# openLRS-APM.net
KiCad netlist of a schematic drawn in EAGLE
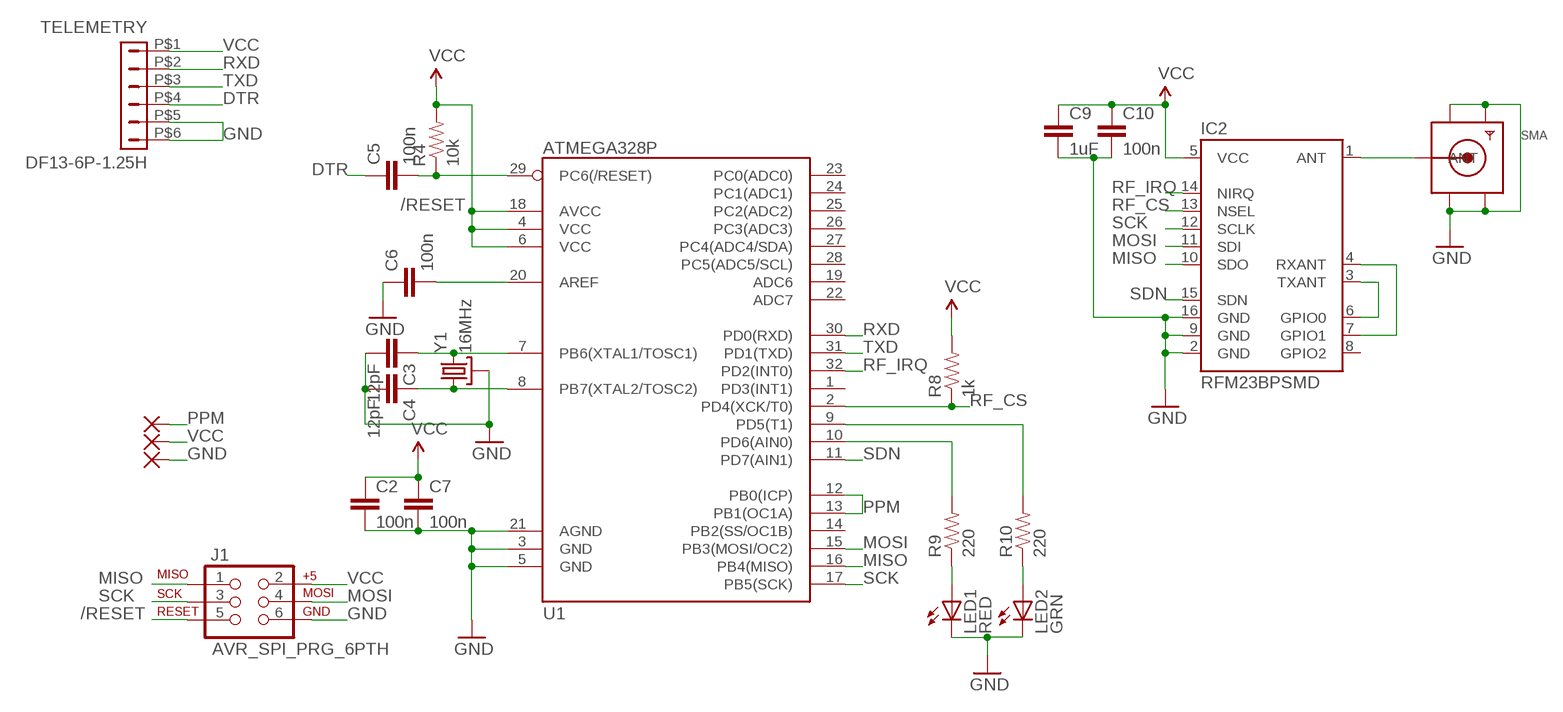
[diagram p0: schematic, sheet 1]

(export (version "E")
  (design (tool "Eeschema 10.0.6"))
  (components
    (comp (ref "C2")
      (value "100n")
      (footprint "eagle-import:0805")
      (libsource (lib "eagle-import") (part "CAP0805"))
    )
    (comp (ref "C3")
      (value "12pF")
      (footprint "eagle-import:0805")
      (libsource (lib "eagle-import") (part "CAP0805"))
    )
    (comp (ref "C4")
      (value "12pF")
      (footprint "eagle-import:0805")
      (libsource (lib "eagle-import") (part "CAP0805"))
    )
    (comp (ref "C5")
      (value "100n")
      (footprint "eagle-import:0805")
      (libsource (lib "eagle-import") (part "CAP0805"))
    )
    (comp (ref "C6")
      (value "100n")
      (footprint "eagle-import:0805")
      (libsource (lib "eagle-import") (part "CAP0805"))
    )
    (comp (ref "C7")
      (value "100n")
      (footprint "eagle-import:0805")
      (libsource (lib "eagle-import") (part "CAP0805"))
    )
    (comp (ref "C9")
      (value "1uF")
      (footprint "eagle-import:0805")
      (libsource (lib "eagle-import") (part "CAP0805"))
    )
    (comp (ref "C10")
      (value "100n")
      (footprint "eagle-import:0805")
      (libsource (lib "eagle-import") (part "CAP0805"))
    )
    (comp (ref "GND")
      (value "WIREPADSMD1,27-254")
      (footprint "eagle-import:SMD1,27-2,54")
      (libsource (lib "eagle-import") (part "WIREPADSMD1,27-254"))
    )
    (comp (ref "IC2")
      (value "RFM23BPSMD")
      (footprint "eagle-import:RFM23BP-S2")
      (libsource (lib "eagle-import") (part "RFM23BPSMD"))
    )
    (comp (ref "J1")
      (value "AVR_SPI_PRG_6PTH")
      (footprint "eagle-import:2X3")
      (libsource (lib "eagle-import") (part "AVR_SPI_PRG_6PTH"))
    )
    (comp (ref "LED1")
      (value "RED")
      (footprint "eagle-import:SML0805")
      (libsource (lib "eagle-import") (part "LEDSML0805"))
    )
    (comp (ref "LED2")
      (value "GRN")
      (footprint "eagle-import:SML0805")
      (libsource (lib "eagle-import") (part "LEDSML0805"))
    )
    (comp (ref "PPM")
      (value "WIREPADSMD1,27-254")
      (footprint "eagle-import:SMD1,27-2,54")
      (libsource (lib "eagle-import") (part "WIREPADSMD1,27-254"))
    )
    (comp (ref "R4")
      (value "10k")
      (footprint "eagle-import:0805")
      (libsource (lib "eagle-import") (part "RESISTOR0805-RES"))
    )
    (comp (ref "R8")
      (value "1k")
      (footprint "eagle-import:0805")
      (libsource (lib "eagle-import") (part "RESISTOR0805-RES"))
    )
    (comp (ref "R9")
      (value "220")
      (footprint "eagle-import:0805")
      (libsource (lib "eagle-import") (part "RESISTOR0805-RES"))
    )
    (comp (ref "R10")
      (value "220")
      (footprint "eagle-import:0805")
      (libsource (lib "eagle-import") (part "RESISTOR0805-RES"))
    )
    (comp (ref "SMA")
      (value "SMACONNECTOR_EDGE")
      (footprint "eagle-import:SMA_EDGELAUNCH")
      (libsource (lib "eagle-import") (part "SMACONNECTOR_EDGE"))
    )
    (comp (ref "TELEMETRY")
      (value "DF13-6P-1.25H")
      (footprint "eagle-import:DF13A-6P-1.25H")
      (libsource (lib "eagle-import") (part "DF13-6P-1.25H"))
    )
    (comp (ref "U1")
      (value "ATMEGA328P")
      (footprint "eagle-import:TQFP32-08")
      (libsource (lib "eagle-import") (part "ATMEGA328_SMT"))
    )
    (comp (ref "VCC")
      (value "WIREPADSMD1,27-254")
      (footprint "eagle-import:SMD1,27-2,54")
      (libsource (lib "eagle-import") (part "WIREPADSMD1,27-254"))
    )
    (comp (ref "Y1")
      (value "16MHz")
      (footprint "eagle-import:CRYSTAL-SMD-5X3")
      (libsource (lib "eagle-import") (part "CRYSTAL3.2X2.5"))
    )
  )
  (nets
    (net (code "1") (name "/DTR") (class "Default")
      (node (ref "C5") (pin "1") (pinfunction "1_1") (pintype "passive"))
      (node (ref "TELEMETRY") (pin "P$4") (pinfunction "4_P$4") (pintype "passive"))
    )
    (net (code "2") (name "/MISO") (class "Default")
      (node (ref "IC2") (pin "10") (pinfunction "SDO_10") (pintype "output"))
      (node (ref "J1") (pin "1") (pinfunction "1_1") (pintype "passive"))
      (node (ref "U1") (pin "16") (pinfunction "PB4(MISO)_16") (pintype "bidirectional"))
    )
    (net (code "3") (name "/MOSI") (class "Default")
      (node (ref "IC2") (pin "11") (pinfunction "SDI_11") (pintype "input"))
      (node (ref "J1") (pin "4") (pinfunction "4_4") (pintype "passive"))
      (node (ref "U1") (pin "15") (pinfunction "PB3(MOSI/OC2)_15") (pintype "bidirectional"))
    )
    (net (code "4") (name "/PPM") (class "Default")
      (node (ref "PPM") (pin "1") (pinfunction "P_1") (pintype "passive"))
      (node (ref "U1") (pin "12") (pinfunction "PB0(ICP)_12") (pintype "bidirectional"))
      (node (ref "U1") (pin "13") (pinfunction "PB1(OC1A)_13") (pintype "bidirectional"))
    )
    (net (code "5") (name "/RF_CS") (class "Default")
      (node (ref "IC2") (pin "13") (pinfunction "NSEL_13") (pintype "input"))
      (node (ref "R8") (pin "1") (pinfunction "1_1") (pintype "passive"))
      (node (ref "U1") (pin "2") (pinfunction "PD4(XCK/T0)_2") (pintype "bidirectional"))
    )
    (net (code "6") (name "/RF_IRQ") (class "Default")
      (node (ref "IC2") (pin "14") (pinfunction "NIRQ_14") (pintype "output"))
      (node (ref "U1") (pin "32") (pinfunction "PD2(INT0)_32") (pintype "bidirectional"))
    )
    (net (code "7") (name "/RXD") (class "Default")
      (node (ref "TELEMETRY") (pin "P$2") (pinfunction "2_P$2") (pintype "passive"))
      (node (ref "U1") (pin "30") (pinfunction "PD0(RXD)_30") (pintype "bidirectional"))
    )
    (net (code "8") (name "/SCK") (class "Default")
      (node (ref "IC2") (pin "12") (pinfunction "SCLK_12") (pintype "input"))
      (node (ref "J1") (pin "3") (pinfunction "3_3") (pintype "passive"))
      (node (ref "U1") (pin "17") (pinfunction "PB5(SCK)_17") (pintype "bidirectional"))
    )
    (net (code "9") (name "/SDN") (class "Default")
      (node (ref "IC2") (pin "15") (pinfunction "SDN_15") (pintype "input"))
      (node (ref "U1") (pin "11") (pinfunction "PD7(AIN1)_11") (pintype "bidirectional"))
    )
    (net (code "10") (name "/TXD") (class "Default")
      (node (ref "TELEMETRY") (pin "P$3") (pinfunction "3_P$3") (pintype "passive"))
      (node (ref "U1") (pin "31") (pinfunction "PD1(TXD)_31") (pintype "bidirectional"))
    )
    (net (code "11") (name "/{slash}RESET") (class "Default")
      (node (ref "C5") (pin "2") (pinfunction "2_2") (pintype "passive"))
      (node (ref "J1") (pin "5") (pinfunction "5_5") (pintype "passive"))
      (node (ref "R4") (pin "1") (pinfunction "1_1") (pintype "passive"))
      (node (ref "U1") (pin "29") (pinfunction "PC6(/RESET)_29") (pintype "bidirectional"))
    )
    (net (code "12") (name "GND") (class "Default")
      (node (ref "C10") (pin "2") (pinfunction "2_2") (pintype "passive"))
      (node (ref "C2") (pin "2") (pinfunction "2_2") (pintype "passive"))
      (node (ref "C3") (pin "2") (pinfunction "2_2") (pintype "passive"))
      (node (ref "C4") (pin "2") (pinfunction "2_2") (pintype "passive"))
      (node (ref "C6") (pin "1") (pinfunction "1_1") (pintype "passive"))
      (node (ref "C7") (pin "2") (pinfunction "2_2") (pintype "passive"))
      (node (ref "C9") (pin "2") (pinfunction "2_2") (pintype "passive"))
      (node (ref "GND") (pin "1") (pinfunction "P_1") (pintype "passive"))
      (node (ref "IC2") (pin "16") (pinfunction "GND_16") (pintype "power_in"))
      (node (ref "IC2") (pin "2") (pinfunction "GND_2") (pintype "power_in"))
      (node (ref "IC2") (pin "9") (pinfunction "GND_9") (pintype "power_in"))
      (node (ref "J1") (pin "6") (pinfunction "6_6") (pintype "passive"))
      (node (ref "LED1") (pin "C") (pinfunction "C_C") (pintype "passive"))
      (node (ref "LED2") (pin "C") (pinfunction "C_C") (pintype "passive"))
      (node (ref "SMA") (pin "GND@1") (pinfunction "GND4_GND@1") (pintype "power_in"))
      (node (ref "SMA") (pin "GND@2") (pinfunction "GND3_GND@2") (pintype "power_in"))
      (node (ref "SMA") (pin "GND@3") (pinfunction "GND2_GND@3") (pintype "power_in"))
      (node (ref "SMA") (pin "GND@4") (pinfunction "GND1_GND@4") (pintype "power_in"))
      (node (ref "TELEMETRY") (pin "P$5") (pinfunction "5_P$5") (pintype "passive"))
      (node (ref "TELEMETRY") (pin "P$6") (pinfunction "6_P$6") (pintype "passive"))
      (node (ref "U1") (pin "21") (pinfunction "AGND_21") (pintype "bidirectional"))
      (node (ref "U1") (pin "3") (pinfunction "GND_3") (pintype "bidirectional"))
      (node (ref "U1") (pin "5") (pinfunction "GND_5") (pintype "bidirectional"))
      (node (ref "Y1") (pin "2") (pinfunction "GND_2") (pintype "power_in"))
      (node (ref "Y1") (pin "4") (pinfunction "GND_4") (pintype "power_in"))
    )
    (net (code "13") (name "Net-(IC2-ANT)") (class "Default")
      (node (ref "IC2") (pin "1") (pinfunction "ANT_1") (pintype "bidirectional"))
      (node (ref "SMA") (pin "P") (pinfunction "ANT_P") (pintype "bidirectional"))
    )
    (net (code "14") (name "Net-(IC2-GPIO0)") (class "Default")
      (node (ref "IC2") (pin "3") (pinfunction "TXANT_3") (pintype "input"))
      (node (ref "IC2") (pin "6") (pinfunction "GPIO0_6") (pintype "bidirectional"))
    )
    (net (code "15") (name "Net-(IC2-GPIO1)") (class "Default")
      (node (ref "IC2") (pin "4") (pinfunction "RXANT_4") (pintype "input"))
      (node (ref "IC2") (pin "7") (pinfunction "GPIO1_7") (pintype "bidirectional"))
    )
    (net (code "16") (name "Net-(LED1-PadA)") (class "Default")
      (node (ref "LED1") (pin "A") (pinfunction "A_A") (pintype "passive"))
      (node (ref "R9") (pin "1") (pinfunction "1_1") (pintype "passive"))
    )
    (net (code "17") (name "Net-(LED2-PadA)") (class "Default")
      (node (ref "LED2") (pin "A") (pinfunction "A_A") (pintype "passive"))
      (node (ref "R10") (pin "1") (pinfunction "1_1") (pintype "passive"))
    )
    (net (code "18") (name "Net-(U1-AREF)") (class "Default")
      (node (ref "C6") (pin "2") (pinfunction "2_2") (pintype "passive"))
      (node (ref "U1") (pin "20") (pinfunction "AREF_20") (pintype "bidirectional"))
    )
    (net (code "19") (name "Net-(U1-PB6(XTAL1{slash}TOSC1))") (class "Default")
      (node (ref "C3") (pin "1") (pinfunction "1_1") (pintype "passive"))
      (node (ref "U1") (pin "7") (pinfunction "PB6(XTAL1/TOSC1)_7") (pintype "bidirectional"))
      (node (ref "Y1") (pin "3") (pinfunction "2_3") (pintype "passive"))
    )
    (net (code "20") (name "Net-(U1-PB7(XTAL2{slash}TOSC2))") (class "Default")
      (node (ref "C4") (pin "1") (pinfunction "1_1") (pintype "passive"))
      (node (ref "U1") (pin "8") (pinfunction "PB7(XTAL2/TOSC2)_8") (pintype "bidirectional"))
      (node (ref "Y1") (pin "1") (pinfunction "1_1") (pintype "passive"))
    )
    (net (code "21") (name "Net-(U1-PD5(T1))") (class "Default")
      (node (ref "R10") (pin "2") (pinfunction "2_2") (pintype "passive"))
      (node (ref "U1") (pin "9") (pinfunction "PD5(T1)_9") (pintype "bidirectional"))
    )
    (net (code "22") (name "Net-(U1-PD6(AIN0))") (class "Default")
      (node (ref "R9") (pin "2") (pinfunction "2_2") (pintype "passive"))
      (node (ref "U1") (pin "10") (pinfunction "PD6(AIN0)_10") (pintype "bidirectional"))
    )
    (net (code "23") (name "VCC") (class "Default")
      (node (ref "C10") (pin "1") (pinfunction "1_1") (pintype "passive"))
      (node (ref "C2") (pin "1") (pinfunction "1_1") (pintype "passive"))
      (node (ref "C7") (pin "1") (pinfunction "1_1") (pintype "passive"))
      (node (ref "C9") (pin "1") (pinfunction "1_1") (pintype "passive"))
      (node (ref "IC2") (pin "5") (pinfunction "VCC_5") (pintype "bidirectional"))
      (node (ref "J1") (pin "2") (pinfunction "2_2") (pintype "passive"))
      (node (ref "R4") (pin "2") (pinfunction "2_2") (pintype "passive"))
      (node (ref "R8") (pin "2") (pinfunction "2_2") (pintype "passive"))
      (node (ref "TELEMETRY") (pin "P$1") (pinfunction "1_P$1") (pintype "passive"))
      (node (ref "U1") (pin "18") (pinfunction "AVCC_18") (pintype "bidirectional"))
      (node (ref "U1") (pin "4") (pinfunction "VCC_4") (pintype "bidirectional"))
      (node (ref "U1") (pin "6") (pinfunction "VCC_6") (pintype "bidirectional"))
      (node (ref "VCC") (pin "1") (pinfunction "P_1") (pintype "passive"))
    )
    (net (code "24") (name "unconnected-(IC2-GPIO2-Pad8)") (class "Default")
      (node (ref "IC2") (pin "8") (pinfunction "GPIO2_8") (pintype "bidirectional"))
    )
    (net (code "25") (name "unconnected-(U1-ADC6-Pad19)") (class "Default")
      (node (ref "U1") (pin "19") (pinfunction "ADC6_19") (pintype "bidirectional"))
    )
    (net (code "26") (name "unconnected-(U1-ADC7-Pad22)") (class "Default")
      (node (ref "U1") (pin "22") (pinfunction "ADC7_22") (pintype "bidirectional"))
    )
    (net (code "27") (name "unconnected-(U1-PB2(SS{slash}OC1B)-Pad14)") (class "Default")
      (node (ref "U1") (pin "14") (pinfunction "PB2(SS/OC1B)_14") (pintype "bidirectional"))
    )
    (net (code "28") (name "unconnected-(U1-PC0(ADC0)-Pad23)") (class "Default")
      (node (ref "U1") (pin "23") (pinfunction "PC0(ADC0)_23") (pintype "bidirectional"))
    )
    (net (code "29") (name "unconnected-(U1-PC1(ADC1)-Pad24)") (class "Default")
      (node (ref "U1") (pin "24") (pinfunction "PC1(ADC1)_24") (pintype "bidirectional"))
    )
    (net (code "30") (name "unconnected-(U1-PC2(ADC2)-Pad25)") (class "Default")
      (node (ref "U1") (pin "25") (pinfunction "PC2(ADC2)_25") (pintype "bidirectional"))
    )
    (net (code "31") (name "unconnected-(U1-PC3(ADC3)-Pad26)") (class "Default")
      (node (ref "U1") (pin "26") (pinfunction "PC3(ADC3)_26") (pintype "bidirectional"))
    )
    (net (code "32") (name "unconnected-(U1-PC4(ADC4{slash}SDA)-Pad27)") (class "Default")
      (node (ref "U1") (pin "27") (pinfunction "PC4(ADC4/SDA)_27") (pintype "bidirectional"))
    )
    (net (code "33") (name "unconnected-(U1-PC5(ADC5{slash}SCL)-Pad28)") (class "Default")
      (node (ref "U1") (pin "28") (pinfunction "PC5(ADC5/SCL)_28") (pintype "bidirectional"))
    )
    (net (code "34") (name "unconnected-(U1-PD3(INT1)-Pad1)") (class "Default")
      (node (ref "U1") (pin "1") (pinfunction "PD3(INT1)_1") (pintype "bidirectional"))
    )
  )
)
